# SCH1001-001-005-320_-_Controller_Flash.net
KiCad netlist of a schematic drawn in EAGLE
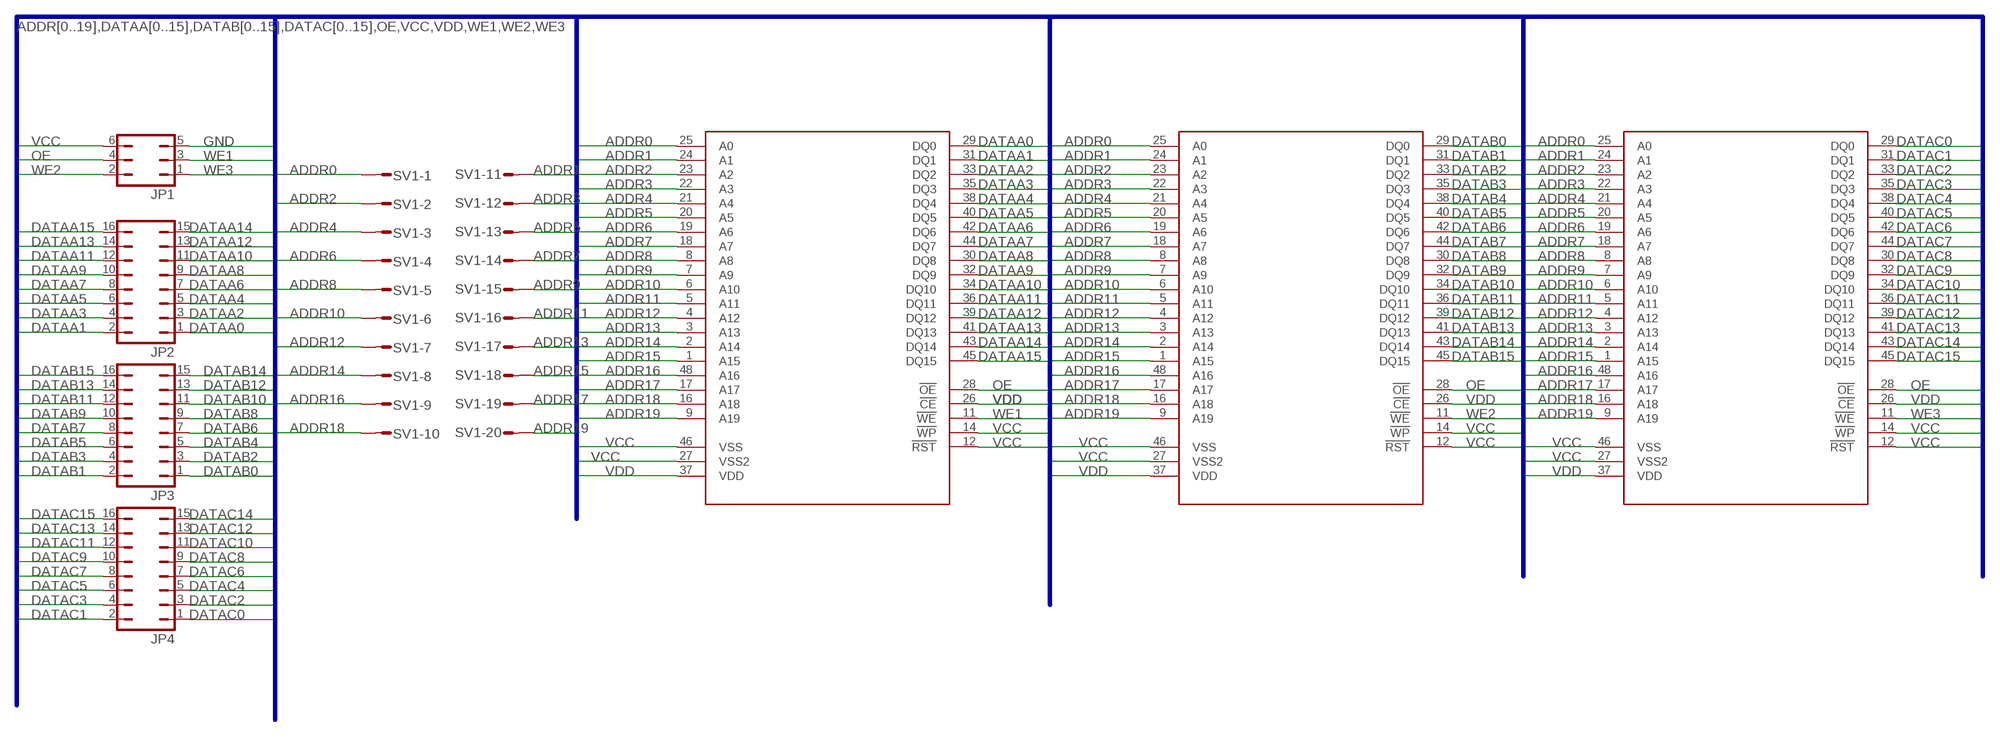
[diagram p0: schematic, sheet 1]

(export (version "E")
  (design (tool "Eeschema 10.0.6"))
  (components
    (comp (ref "JP1")
      (value "JP3Q")
      (footprint "eagle-import:JP3Q")
      (libsource (lib "eagle-import") (part "JP3Q"))
    )
    (comp (ref "JP2")
      (value "JP8Q")
      (footprint "eagle-import:JP8Q")
      (libsource (lib "eagle-import") (part "JP8Q"))
    )
    (comp (ref "JP3")
      (value "JP8Q")
      (footprint "eagle-import:JP8Q")
      (libsource (lib "eagle-import") (part "JP8Q"))
    )
    (comp (ref "JP4")
      (value "JP8Q")
      (footprint "eagle-import:JP8Q")
      (libsource (lib "eagle-import") (part "JP8Q"))
    )
    (comp (ref "SV1")
      (value "S20P")
      (footprint "eagle-import:S20P")
      (libsource (lib "eagle-import") (part "S20P"))
    )
    (comp (ref "U$1")
      (value "SST39VF1602-70-4I-EKE")
      (footprint "eagle-import:TSOP48")
      (libsource (lib "eagle-import") (part "SST39VF1602-70-4I-EKE"))
    )
    (comp (ref "U$2")
      (value "SST39VF1602-70-4I-EKE")
      (footprint "eagle-import:TSOP48")
      (libsource (lib "eagle-import") (part "SST39VF1602-70-4I-EKE"))
    )
    (comp (ref "U$3")
      (value "SST39VF1602-70-4I-EKE")
      (footprint "eagle-import:TSOP48")
      (libsource (lib "eagle-import") (part "SST39VF1602-70-4I-EKE"))
    )
  )
  (nets
    (net (code "1") (name "/ADDR0") (class "Default")
      (node (ref "SV1") (pin "1") (pinfunction "S_1") (pintype "passive"))
      (node (ref "U$1") (pin "25") (pinfunction "A0_25") (pintype "bidirectional"))
      (node (ref "U$2") (pin "25") (pinfunction "A0_25") (pintype "bidirectional"))
      (node (ref "U$3") (pin "25") (pinfunction "A0_25") (pintype "bidirectional"))
    )
    (net (code "2") (name "/ADDR1") (class "Default")
      (node (ref "SV1") (pin "11") (pinfunction "S_11") (pintype "passive"))
      (node (ref "U$1") (pin "24") (pinfunction "A1_24") (pintype "bidirectional"))
      (node (ref "U$2") (pin "24") (pinfunction "A1_24") (pintype "bidirectional"))
      (node (ref "U$3") (pin "24") (pinfunction "A1_24") (pintype "bidirectional"))
    )
    (net (code "3") (name "/ADDR2") (class "Default")
      (node (ref "SV1") (pin "2") (pinfunction "S_2") (pintype "passive"))
      (node (ref "U$1") (pin "23") (pinfunction "A2_23") (pintype "bidirectional"))
      (node (ref "U$2") (pin "23") (pinfunction "A2_23") (pintype "bidirectional"))
      (node (ref "U$3") (pin "23") (pinfunction "A2_23") (pintype "bidirectional"))
    )
    (net (code "4") (name "/ADDR3") (class "Default")
      (node (ref "SV1") (pin "12") (pinfunction "S_12") (pintype "passive"))
      (node (ref "U$1") (pin "22") (pinfunction "A3_22") (pintype "bidirectional"))
      (node (ref "U$2") (pin "22") (pinfunction "A3_22") (pintype "bidirectional"))
      (node (ref "U$3") (pin "22") (pinfunction "A3_22") (pintype "bidirectional"))
    )
    (net (code "5") (name "/ADDR4") (class "Default")
      (node (ref "SV1") (pin "3") (pinfunction "S_3") (pintype "passive"))
      (node (ref "U$1") (pin "21") (pinfunction "A4_21") (pintype "bidirectional"))
      (node (ref "U$2") (pin "21") (pinfunction "A4_21") (pintype "bidirectional"))
      (node (ref "U$3") (pin "21") (pinfunction "A4_21") (pintype "bidirectional"))
    )
    (net (code "6") (name "/ADDR5") (class "Default")
      (node (ref "SV1") (pin "13") (pinfunction "S_13") (pintype "passive"))
      (node (ref "U$1") (pin "20") (pinfunction "A5_20") (pintype "bidirectional"))
      (node (ref "U$2") (pin "20") (pinfunction "A5_20") (pintype "bidirectional"))
      (node (ref "U$3") (pin "20") (pinfunction "A5_20") (pintype "bidirectional"))
    )
    (net (code "7") (name "/ADDR6") (class "Default")
      (node (ref "SV1") (pin "4") (pinfunction "S_4") (pintype "passive"))
      (node (ref "U$1") (pin "19") (pinfunction "A6_19") (pintype "bidirectional"))
      (node (ref "U$2") (pin "19") (pinfunction "A6_19") (pintype "bidirectional"))
      (node (ref "U$3") (pin "19") (pinfunction "A6_19") (pintype "bidirectional"))
    )
    (net (code "8") (name "/ADDR7") (class "Default")
      (node (ref "SV1") (pin "14") (pinfunction "S_14") (pintype "passive"))
      (node (ref "U$1") (pin "18") (pinfunction "A7_18") (pintype "bidirectional"))
      (node (ref "U$2") (pin "18") (pinfunction "A7_18") (pintype "bidirectional"))
      (node (ref "U$3") (pin "18") (pinfunction "A7_18") (pintype "bidirectional"))
    )
    (net (code "9") (name "/ADDR8") (class "Default")
      (node (ref "SV1") (pin "5") (pinfunction "S_5") (pintype "passive"))
      (node (ref "U$1") (pin "8") (pinfunction "A8_8") (pintype "bidirectional"))
      (node (ref "U$2") (pin "8") (pinfunction "A8_8") (pintype "bidirectional"))
      (node (ref "U$3") (pin "8") (pinfunction "A8_8") (pintype "bidirectional"))
    )
    (net (code "10") (name "/ADDR9") (class "Default")
      (node (ref "SV1") (pin "15") (pinfunction "S_15") (pintype "passive"))
      (node (ref "U$1") (pin "7") (pinfunction "A9_7") (pintype "bidirectional"))
      (node (ref "U$2") (pin "7") (pinfunction "A9_7") (pintype "bidirectional"))
      (node (ref "U$3") (pin "7") (pinfunction "A9_7") (pintype "bidirectional"))
    )
    (net (code "11") (name "/ADDR10") (class "Default")
      (node (ref "SV1") (pin "6") (pinfunction "S_6") (pintype "passive"))
      (node (ref "U$1") (pin "6") (pinfunction "A10_6") (pintype "bidirectional"))
      (node (ref "U$2") (pin "6") (pinfunction "A10_6") (pintype "bidirectional"))
      (node (ref "U$3") (pin "6") (pinfunction "A10_6") (pintype "bidirectional"))
    )
    (net (code "12") (name "/ADDR11") (class "Default")
      (node (ref "SV1") (pin "16") (pinfunction "S_16") (pintype "passive"))
      (node (ref "U$1") (pin "5") (pinfunction "A11_5") (pintype "bidirectional"))
      (node (ref "U$2") (pin "5") (pinfunction "A11_5") (pintype "bidirectional"))
      (node (ref "U$3") (pin "5") (pinfunction "A11_5") (pintype "bidirectional"))
    )
    (net (code "13") (name "/ADDR12") (class "Default")
      (node (ref "SV1") (pin "7") (pinfunction "S_7") (pintype "passive"))
      (node (ref "U$1") (pin "4") (pinfunction "A12_4") (pintype "bidirectional"))
      (node (ref "U$2") (pin "4") (pinfunction "A12_4") (pintype "bidirectional"))
      (node (ref "U$3") (pin "4") (pinfunction "A12_4") (pintype "bidirectional"))
    )
    (net (code "14") (name "/ADDR13") (class "Default")
      (node (ref "SV1") (pin "17") (pinfunction "S_17") (pintype "passive"))
      (node (ref "U$1") (pin "3") (pinfunction "A13_3") (pintype "bidirectional"))
      (node (ref "U$2") (pin "3") (pinfunction "A13_3") (pintype "bidirectional"))
      (node (ref "U$3") (pin "3") (pinfunction "A13_3") (pintype "bidirectional"))
    )
    (net (code "15") (name "/ADDR14") (class "Default")
      (node (ref "SV1") (pin "8") (pinfunction "S_8") (pintype "passive"))
      (node (ref "U$1") (pin "2") (pinfunction "A14_2") (pintype "bidirectional"))
      (node (ref "U$2") (pin "2") (pinfunction "A14_2") (pintype "bidirectional"))
      (node (ref "U$3") (pin "2") (pinfunction "A14_2") (pintype "bidirectional"))
    )
    (net (code "16") (name "/ADDR15") (class "Default")
      (node (ref "SV1") (pin "18") (pinfunction "S_18") (pintype "passive"))
      (node (ref "U$1") (pin "1") (pinfunction "A15_1") (pintype "bidirectional"))
      (node (ref "U$2") (pin "1") (pinfunction "A15_1") (pintype "bidirectional"))
      (node (ref "U$3") (pin "1") (pinfunction "A15_1") (pintype "bidirectional"))
    )
    (net (code "17") (name "/ADDR16") (class "Default")
      (node (ref "SV1") (pin "9") (pinfunction "S_9") (pintype "passive"))
      (node (ref "U$1") (pin "48") (pinfunction "A16_48") (pintype "bidirectional"))
      (node (ref "U$2") (pin "48") (pinfunction "A16_48") (pintype "bidirectional"))
      (node (ref "U$3") (pin "48") (pinfunction "A16_48") (pintype "bidirectional"))
    )
    (net (code "18") (name "/ADDR17") (class "Default")
      (node (ref "SV1") (pin "19") (pinfunction "S_19") (pintype "passive"))
      (node (ref "U$1") (pin "17") (pinfunction "A17_17") (pintype "bidirectional"))
      (node (ref "U$2") (pin "17") (pinfunction "A17_17") (pintype "bidirectional"))
      (node (ref "U$3") (pin "17") (pinfunction "A17_17") (pintype "bidirectional"))
    )
    (net (code "19") (name "/ADDR18") (class "Default")
      (node (ref "SV1") (pin "10") (pinfunction "S_10") (pintype "passive"))
      (node (ref "U$1") (pin "16") (pinfunction "A18_16") (pintype "bidirectional"))
      (node (ref "U$2") (pin "16") (pinfunction "A18_16") (pintype "bidirectional"))
      (node (ref "U$3") (pin "16") (pinfunction "A18_16") (pintype "bidirectional"))
    )
    (net (code "20") (name "/ADDR19") (class "Default")
      (node (ref "SV1") (pin "20") (pinfunction "S_20") (pintype "passive"))
      (node (ref "U$1") (pin "9") (pinfunction "A19_9") (pintype "bidirectional"))
      (node (ref "U$2") (pin "9") (pinfunction "A19_9") (pintype "bidirectional"))
      (node (ref "U$3") (pin "9") (pinfunction "A19_9") (pintype "bidirectional"))
    )
    (net (code "21") (name "/DATAA0") (class "Default")
      (node (ref "JP2") (pin "1") (pinfunction "1_1") (pintype "passive"))
      (node (ref "U$1") (pin "29") (pinfunction "DQ0_29") (pintype "bidirectional"))
    )
    (net (code "22") (name "/DATAA1") (class "Default")
      (node (ref "JP2") (pin "2") (pinfunction "2_2") (pintype "passive"))
      (node (ref "U$1") (pin "31") (pinfunction "DQ1_31") (pintype "bidirectional"))
    )
    (net (code "23") (name "/DATAA2") (class "Default")
      (node (ref "JP2") (pin "3") (pinfunction "3_3") (pintype "passive"))
      (node (ref "U$1") (pin "33") (pinfunction "DQ2_33") (pintype "bidirectional"))
    )
    (net (code "24") (name "/DATAA3") (class "Default")
      (node (ref "JP2") (pin "4") (pinfunction "4_4") (pintype "passive"))
      (node (ref "U$1") (pin "35") (pinfunction "DQ3_35") (pintype "bidirectional"))
    )
    (net (code "25") (name "/DATAA4") (class "Default")
      (node (ref "JP2") (pin "5") (pinfunction "5_5") (pintype "passive"))
      (node (ref "U$1") (pin "38") (pinfunction "DQ4_38") (pintype "bidirectional"))
    )
    (net (code "26") (name "/DATAA5") (class "Default")
      (node (ref "JP2") (pin "6") (pinfunction "6_6") (pintype "passive"))
      (node (ref "U$1") (pin "40") (pinfunction "DQ5_40") (pintype "bidirectional"))
    )
    (net (code "27") (name "/DATAA6") (class "Default")
      (node (ref "JP2") (pin "7") (pinfunction "7_7") (pintype "passive"))
      (node (ref "U$1") (pin "42") (pinfunction "DQ6_42") (pintype "bidirectional"))
    )
    (net (code "28") (name "/DATAA7") (class "Default")
      (node (ref "JP2") (pin "8") (pinfunction "8_8") (pintype "passive"))
      (node (ref "U$1") (pin "44") (pinfunction "DQ7_44") (pintype "bidirectional"))
    )
    (net (code "29") (name "/DATAA8") (class "Default")
      (node (ref "JP2") (pin "9") (pinfunction "9_9") (pintype "passive"))
      (node (ref "U$1") (pin "30") (pinfunction "DQ8_30") (pintype "bidirectional"))
    )
    (net (code "30") (name "/DATAA9") (class "Default")
      (node (ref "JP2") (pin "10") (pinfunction "10_10") (pintype "passive"))
      (node (ref "U$1") (pin "32") (pinfunction "DQ9_32") (pintype "bidirectional"))
    )
    (net (code "31") (name "/DATAA10") (class "Default")
      (node (ref "JP2") (pin "11") (pinfunction "11_11") (pintype "passive"))
      (node (ref "U$1") (pin "34") (pinfunction "DQ10_34") (pintype "bidirectional"))
    )
    (net (code "32") (name "/DATAA11") (class "Default")
      (node (ref "JP2") (pin "12") (pinfunction "12_12") (pintype "passive"))
      (node (ref "U$1") (pin "36") (pinfunction "DQ11_36") (pintype "bidirectional"))
    )
    (net (code "33") (name "/DATAA12") (class "Default")
      (node (ref "JP2") (pin "13") (pinfunction "13_13") (pintype "passive"))
      (node (ref "U$1") (pin "39") (pinfunction "DQ12_39") (pintype "bidirectional"))
    )
    (net (code "34") (name "/DATAA13") (class "Default")
      (node (ref "JP2") (pin "14") (pinfunction "14_14") (pintype "passive"))
      (node (ref "U$1") (pin "41") (pinfunction "DQ13_41") (pintype "bidirectional"))
    )
    (net (code "35") (name "/DATAA14") (class "Default")
      (node (ref "JP2") (pin "15") (pinfunction "15_15") (pintype "passive"))
      (node (ref "U$1") (pin "43") (pinfunction "DQ14_43") (pintype "bidirectional"))
    )
    (net (code "36") (name "/DATAA15") (class "Default")
      (node (ref "JP2") (pin "16") (pinfunction "16_16") (pintype "passive"))
      (node (ref "U$1") (pin "45") (pinfunction "DQ15_45") (pintype "bidirectional"))
    )
    (net (code "37") (name "/DATAB0") (class "Default")
      (node (ref "JP3") (pin "1") (pinfunction "1_1") (pintype "passive"))
      (node (ref "U$2") (pin "29") (pinfunction "DQ0_29") (pintype "bidirectional"))
    )
    (net (code "38") (name "/DATAB1") (class "Default")
      (node (ref "JP3") (pin "2") (pinfunction "2_2") (pintype "passive"))
      (node (ref "U$2") (pin "31") (pinfunction "DQ1_31") (pintype "bidirectional"))
    )
    (net (code "39") (name "/DATAB2") (class "Default")
      (node (ref "JP3") (pin "3") (pinfunction "3_3") (pintype "passive"))
      (node (ref "U$2") (pin "33") (pinfunction "DQ2_33") (pintype "bidirectional"))
    )
    (net (code "40") (name "/DATAB3") (class "Default")
      (node (ref "JP3") (pin "4") (pinfunction "4_4") (pintype "passive"))
      (node (ref "U$2") (pin "35") (pinfunction "DQ3_35") (pintype "bidirectional"))
    )
    (net (code "41") (name "/DATAB4") (class "Default")
      (node (ref "JP3") (pin "5") (pinfunction "5_5") (pintype "passive"))
      (node (ref "U$2") (pin "38") (pinfunction "DQ4_38") (pintype "bidirectional"))
    )
    (net (code "42") (name "/DATAB5") (class "Default")
      (node (ref "JP3") (pin "6") (pinfunction "6_6") (pintype "passive"))
      (node (ref "U$2") (pin "40") (pinfunction "DQ5_40") (pintype "bidirectional"))
    )
    (net (code "43") (name "/DATAB6") (class "Default")
      (node (ref "JP3") (pin "7") (pinfunction "7_7") (pintype "passive"))
      (node (ref "U$2") (pin "42") (pinfunction "DQ6_42") (pintype "bidirectional"))
    )
    (net (code "44") (name "/DATAB7") (class "Default")
      (node (ref "JP3") (pin "8") (pinfunction "8_8") (pintype "passive"))
      (node (ref "U$2") (pin "44") (pinfunction "DQ7_44") (pintype "bidirectional"))
    )
    (net (code "45") (name "/DATAB8") (class "Default")
      (node (ref "JP3") (pin "9") (pinfunction "9_9") (pintype "passive"))
      (node (ref "U$2") (pin "30") (pinfunction "DQ8_30") (pintype "bidirectional"))
    )
    (net (code "46") (name "/DATAB9") (class "Default")
      (node (ref "JP3") (pin "10") (pinfunction "10_10") (pintype "passive"))
      (node (ref "U$2") (pin "32") (pinfunction "DQ9_32") (pintype "bidirectional"))
    )
    (net (code "47") (name "/DATAB10") (class "Default")
      (node (ref "JP3") (pin "11") (pinfunction "11_11") (pintype "passive"))
      (node (ref "U$2") (pin "34") (pinfunction "DQ10_34") (pintype "bidirectional"))
    )
    (net (code "48") (name "/DATAB11") (class "Default")
      (node (ref "JP3") (pin "12") (pinfunction "12_12") (pintype "passive"))
      (node (ref "U$2") (pin "36") (pinfunction "DQ11_36") (pintype "bidirectional"))
    )
    (net (code "49") (name "/DATAB12") (class "Default")
      (node (ref "JP3") (pin "13") (pinfunction "13_13") (pintype "passive"))
      (node (ref "U$2") (pin "39") (pinfunction "DQ12_39") (pintype "bidirectional"))
    )
    (net (code "50") (name "/DATAB13") (class "Default")
      (node (ref "JP3") (pin "14") (pinfunction "14_14") (pintype "passive"))
      (node (ref "U$2") (pin "41") (pinfunction "DQ13_41") (pintype "bidirectional"))
    )
    (net (code "51") (name "/DATAB14") (class "Default")
      (node (ref "JP3") (pin "15") (pinfunction "15_15") (pintype "passive"))
      (node (ref "U$2") (pin "43") (pinfunction "DQ14_43") (pintype "bidirectional"))
    )
    (net (code "52") (name "/DATAB15") (class "Default")
      (node (ref "JP3") (pin "16") (pinfunction "16_16") (pintype "passive"))
      (node (ref "U$2") (pin "45") (pinfunction "DQ15_45") (pintype "bidirectional"))
    )
    (net (code "53") (name "/DATAC0") (class "Default")
      (node (ref "JP4") (pin "1") (pinfunction "1_1") (pintype "passive"))
      (node (ref "U$3") (pin "29") (pinfunction "DQ0_29") (pintype "bidirectional"))
    )
    (net (code "54") (name "/DATAC1") (class "Default")
      (node (ref "JP4") (pin "2") (pinfunction "2_2") (pintype "passive"))
      (node (ref "U$3") (pin "31") (pinfunction "DQ1_31") (pintype "bidirectional"))
    )
    (net (code "55") (name "/DATAC2") (class "Default")
      (node (ref "JP4") (pin "3") (pinfunction "3_3") (pintype "passive"))
      (node (ref "U$3") (pin "33") (pinfunction "DQ2_33") (pintype "bidirectional"))
    )
    (net (code "56") (name "/DATAC3") (class "Default")
      (node (ref "JP4") (pin "4") (pinfunction "4_4") (pintype "passive"))
      (node (ref "U$3") (pin "35") (pinfunction "DQ3_35") (pintype "bidirectional"))
    )
    (net (code "57") (name "/DATAC4") (class "Default")
      (node (ref "JP4") (pin "5") (pinfunction "5_5") (pintype "passive"))
      (node (ref "U$3") (pin "38") (pinfunction "DQ4_38") (pintype "bidirectional"))
    )
    (net (code "58") (name "/DATAC5") (class "Default")
      (node (ref "JP4") (pin "6") (pinfunction "6_6") (pintype "passive"))
      (node (ref "U$3") (pin "40") (pinfunction "DQ5_40") (pintype "bidirectional"))
    )
    (net (code "59") (name "/DATAC6") (class "Default")
      (node (ref "JP4") (pin "7") (pinfunction "7_7") (pintype "passive"))
      (node (ref "U$3") (pin "42") (pinfunction "DQ6_42") (pintype "bidirectional"))
    )
    (net (code "60") (name "/DATAC7") (class "Default")
      (node (ref "JP4") (pin "8") (pinfunction "8_8") (pintype "passive"))
      (node (ref "U$3") (pin "44") (pinfunction "DQ7_44") (pintype "bidirectional"))
    )
    (net (code "61") (name "/DATAC8") (class "Default")
      (node (ref "JP4") (pin "9") (pinfunction "9_9") (pintype "passive"))
      (node (ref "U$3") (pin "30") (pinfunction "DQ8_30") (pintype "bidirectional"))
    )
    (net (code "62") (name "/DATAC9") (class "Default")
      (node (ref "JP4") (pin "10") (pinfunction "10_10") (pintype "passive"))
      (node (ref "U$3") (pin "32") (pinfunction "DQ9_32") (pintype "bidirectional"))
    )
    (net (code "63") (name "/DATAC10") (class "Default")
      (node (ref "JP4") (pin "11") (pinfunction "11_11") (pintype "passive"))
      (node (ref "U$3") (pin "34") (pinfunction "DQ10_34") (pintype "bidirectional"))
    )
    (net (code "64") (name "/DATAC11") (class "Default")
      (node (ref "JP4") (pin "12") (pinfunction "12_12") (pintype "passive"))
      (node (ref "U$3") (pin "36") (pinfunction "DQ11_36") (pintype "bidirectional"))
    )
    (net (code "65") (name "/DATAC12") (class "Default")
      (node (ref "JP4") (pin "13") (pinfunction "13_13") (pintype "passive"))
      (node (ref "U$3") (pin "39") (pinfunction "DQ12_39") (pintype "bidirectional"))
    )
    (net (code "66") (name "/DATAC13") (class "Default")
      (node (ref "JP4") (pin "14") (pinfunction "14_14") (pintype "passive"))
      (node (ref "U$3") (pin "41") (pinfunction "DQ13_41") (pintype "bidirectional"))
    )
    (net (code "67") (name "/DATAC14") (class "Default")
      (node (ref "JP4") (pin "15") (pinfunction "15_15") (pintype "passive"))
      (node (ref "U$3") (pin "43") (pinfunction "DQ14_43") (pintype "bidirectional"))
    )
    (net (code "68") (name "/DATAC15") (class "Default")
      (node (ref "JP4") (pin "16") (pinfunction "16_16") (pintype "passive"))
      (node (ref "U$3") (pin "45") (pinfunction "DQ15_45") (pintype "bidirectional"))
    )
    (net (code "69") (name "/GND") (class "Default")
      (node (ref "JP1") (pin "5") (pinfunction "5_5") (pintype "passive"))
    )
    (net (code "70") (name "/OE") (class "Default")
      (node (ref "JP1") (pin "4") (pinfunction "4_4") (pintype "passive"))
      (node (ref "U$1") (pin "28") (pinfunction "~{OE}_28") (pintype "bidirectional"))
      (node (ref "U$2") (pin "28") (pinfunction "~{OE}_28") (pintype "bidirectional"))
      (node (ref "U$3") (pin "28") (pinfunction "~{OE}_28") (pintype "bidirectional"))
    )
    (net (code "71") (name "/VCC") (class "Default")
      (node (ref "JP1") (pin "6") (pinfunction "6_6") (pintype "passive"))
      (node (ref "U$1") (pin "12") (pinfunction "~{RST}_12") (pintype "bidirectional"))
      (node (ref "U$1") (pin "14") (pinfunction "~{WP}_14") (pintype "bidirectional"))
      (node (ref "U$1") (pin "27") (pinfunction "VSS2_27") (pintype "bidirectional"))
      (node (ref "U$1") (pin "46") (pinfunction "VSS_46") (pintype "bidirectional"))
      (node (ref "U$2") (pin "12") (pinfunction "~{RST}_12") (pintype "bidirectional"))
      (node (ref "U$2") (pin "14") (pinfunction "~{WP}_14") (pintype "bidirectional"))
      (node (ref "U$2") (pin "27") (pinfunction "VSS2_27") (pintype "bidirectional"))
      (node (ref "U$2") (pin "46") (pinfunction "VSS_46") (pintype "bidirectional"))
      (node (ref "U$3") (pin "12") (pinfunction "~{RST}_12") (pintype "bidirectional"))
      (node (ref "U$3") (pin "14") (pinfunction "~{WP}_14") (pintype "bidirectional"))
      (node (ref "U$3") (pin "27") (pinfunction "VSS2_27") (pintype "bidirectional"))
      (node (ref "U$3") (pin "46") (pinfunction "VSS_46") (pintype "bidirectional"))
    )
    (net (code "72") (name "/VDD") (class "Default")
      (node (ref "U$1") (pin "26") (pinfunction "~{CE}_26") (pintype "bidirectional"))
      (node (ref "U$1") (pin "37") (pinfunction "VDD_37") (pintype "bidirectional"))
      (node (ref "U$2") (pin "26") (pinfunction "~{CE}_26") (pintype "bidirectional"))
      (node (ref "U$2") (pin "37") (pinfunction "VDD_37") (pintype "bidirectional"))
      (node (ref "U$3") (pin "26") (pinfunction "~{CE}_26") (pintype "bidirectional"))
      (node (ref "U$3") (pin "37") (pinfunction "VDD_37") (pintype "bidirectional"))
    )
    (net (code "73") (name "/WE1") (class "Default")
      (node (ref "JP1") (pin "3") (pinfunction "3_3") (pintype "passive"))
      (node (ref "U$1") (pin "11") (pinfunction "~{WE}_11") (pintype "bidirectional"))
    )
    (net (code "74") (name "/WE2") (class "Default")
      (node (ref "JP1") (pin "2") (pinfunction "2_2") (pintype "passive"))
      (node (ref "U$2") (pin "11") (pinfunction "~{WE}_11") (pintype "bidirectional"))
    )
    (net (code "75") (name "/WE3") (class "Default")
      (node (ref "JP1") (pin "1") (pinfunction "1_1") (pintype "passive"))
      (node (ref "U$3") (pin "11") (pinfunction "~{WE}_11") (pintype "bidirectional"))
    )
  )
)
